# ADS1271_top.net
KiCad netlist of a schematic drawn in EAGLE
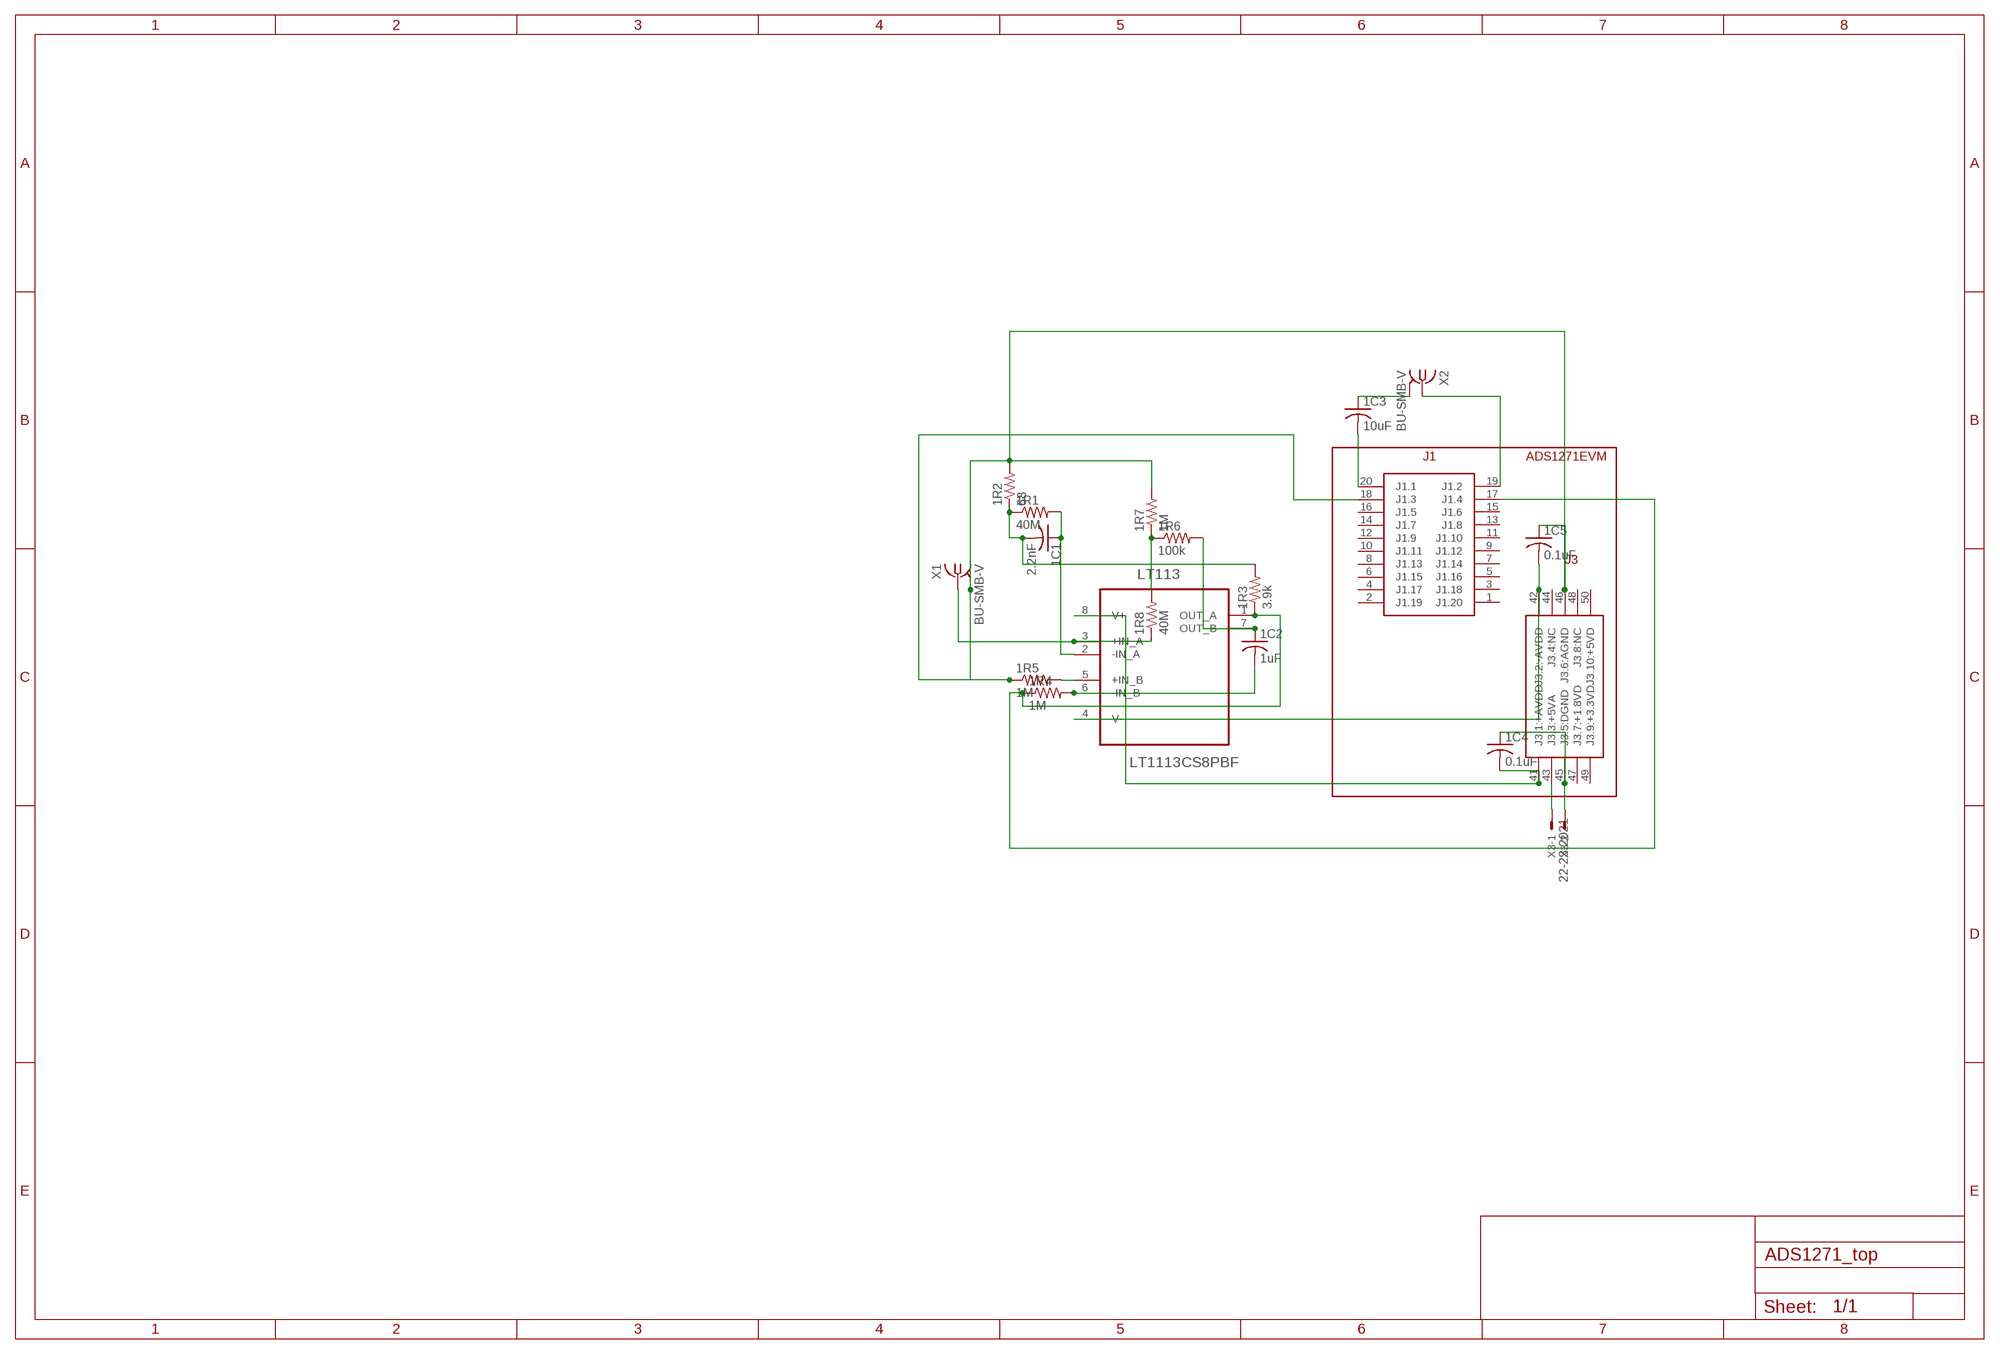
[diagram p0: schematic, sheet 1]

(export (version "E")
  (design (tool "Eeschema 10.0.6"))
  (components
    (comp (ref "1C1")
      (value "2.2nF")
      (footprint "eagle-import:ADAFRUIT_C0805K")
      (libsource (lib "eagle-import") (part "ADAFRUIT_C-USC0805K"))
    )
    (comp (ref "1C2")
      (value "1uF")
      (footprint "eagle-import:ADAFRUIT_C0805K")
      (libsource (lib "eagle-import") (part "ADAFRUIT_C-USC0805K"))
    )
    (comp (ref "1C3")
      (value "10uF")
      (footprint "eagle-import:ADAFRUIT_C0805K")
      (libsource (lib "eagle-import") (part "ADAFRUIT_C-USC0805K"))
    )
    (comp (ref "1C4")
      (value "0.1uF")
      (footprint "eagle-import:ADAFRUIT_C0805K")
      (libsource (lib "eagle-import") (part "ADAFRUIT_C-USC0805K"))
    )
    (comp (ref "1C5")
      (value "0.1uF")
      (footprint "eagle-import:ADAFRUIT_C0805K")
      (libsource (lib "eagle-import") (part "ADAFRUIT_C-USC0805K"))
    )
    (comp (ref "1R1")
      (value "40M")
      (footprint "eagle-import:ADAFRUIT_R0805")
      (libsource (lib "eagle-import") (part "ADAFRUIT_R-US_R0805"))
    )
    (comp (ref "1R2")
      (value "68")
      (footprint "eagle-import:ADAFRUIT_R0805")
      (libsource (lib "eagle-import") (part "ADAFRUIT_R-US_R0805"))
    )
    (comp (ref "1R3")
      (value "3.9k")
      (footprint "eagle-import:ADAFRUIT_R0805")
      (libsource (lib "eagle-import") (part "ADAFRUIT_R-US_R0805"))
    )
    (comp (ref "1R4")
      (value "1M")
      (footprint "eagle-import:ADAFRUIT_R0805")
      (libsource (lib "eagle-import") (part "ADAFRUIT_R-US_R0805"))
    )
    (comp (ref "1R5")
      (value "1M")
      (footprint "eagle-import:ADAFRUIT_R0805")
      (libsource (lib "eagle-import") (part "ADAFRUIT_R-US_R0805"))
    )
    (comp (ref "1R6")
      (value "100k")
      (footprint "eagle-import:ADAFRUIT_R0805")
      (libsource (lib "eagle-import") (part "ADAFRUIT_R-US_R0805"))
    )
    (comp (ref "1R7")
      (value "1M")
      (footprint "eagle-import:ADAFRUIT_R0805")
      (libsource (lib "eagle-import") (part "ADAFRUIT_R-US_R0805"))
    )
    (comp (ref "1R8")
      (value "40M")
      (footprint "eagle-import:ADAFRUIT_R0805")
      (libsource (lib "eagle-import") (part "ADAFRUIT_R-US_R0805"))
    )
    (comp (ref "ADS1271_CONNECTORS")
      (value "BENS_LIBRARY_ADS1271EVM_PART")
      (footprint "eagle-import:BENS_LIBRARY_ADS1271EVM_PART")
      (libsource (lib "eagle-import") (part "BENS_LIBRARY_ADS1271EVM_PART"))
    )
    (comp (ref "LT113")
      (value "LT1113CS8PBF")
      (footprint "eagle-import:SOIC127P600X175-8N")
      (fields (field (name "MPN") "LT1113CS8#PBF"))
      (libsource (lib "eagle-import") (part "LT1113CS8PBF"))
    )
    (comp (ref "X1")
      (value "BU-SMB-V")
      (footprint "eagle-import:BU-SMB-V")
      (libsource (lib "eagle-import") (part "BU-SMB-V"))
    )
    (comp (ref "X2")
      (value "BU-SMB-V")
      (footprint "eagle-import:BU-SMB-V")
      (libsource (lib "eagle-import") (part "BU-SMB-V"))
    )
    (comp (ref "X3")
      (value "22-23-2021")
      (footprint "eagle-import:22-23-2021")
      (fields (field (name "MF") "MOLEX"))
      (libsource (lib "eagle-import") (part "22-23-2021"))
    )
  )
  (nets
    (net (code "1") (name "/ADC1_POS") (class "Default")
      (node (ref "1C4") (pin "1") (pinfunction "1_1") (pintype "passive"))
      (node (ref "1C5") (pin "1") (pinfunction "1_1") (pintype "passive"))
      (node (ref "1R2") (pin "2") (pinfunction "2_2") (pintype "passive"))
      (node (ref "1R5") (pin "1") (pinfunction "1_1") (pintype "passive"))
      (node (ref "1R7") (pin "2") (pinfunction "2_2") (pintype "passive"))
      (node (ref "ADS1271_CONNECTORS") (pin "18") (pinfunction "J1.3_18") (pintype "bidirectional"))
      (node (ref "ADS1271_CONNECTORS") (pin "45") (pinfunction "J3.5:DGND_45") (pintype "bidirectional"))
      (node (ref "ADS1271_CONNECTORS") (pin "46") (pinfunction "J3.6:AGND_46") (pintype "bidirectional"))
      (node (ref "X1") (pin "2") (pinfunction "2_2") (pintype "passive"))
      (node (ref "X1") (pin "3") (pinfunction "2_3") (pintype "passive"))
      (node (ref "X1") (pin "4") (pinfunction "2_4") (pintype "passive"))
      (node (ref "X1") (pin "5") (pinfunction "2_5") (pintype "passive"))
      (node (ref "X3") (pin "2") (pinfunction "S_2") (pintype "passive"))
    )
    (net (code "2") (name "Net-(1C1-Pad2)") (class "Default")
      (node (ref "1C1") (pin "2") (pinfunction "2_2") (pintype "passive"))
      (node (ref "1R1") (pin "1") (pinfunction "1_1") (pintype "passive"))
      (node (ref "1R2") (pin "1") (pinfunction "1_1") (pintype "passive"))
      (node (ref "1R3") (pin "2") (pinfunction "2_2") (pintype "passive"))
    )
    (net (code "3") (name "Net-(1C3-Pad1)") (class "Default")
      (node (ref "1C3") (pin "1") (pinfunction "1_1") (pintype "passive"))
      (node (ref "X2") (pin "2") (pinfunction "2_2") (pintype "passive"))
      (node (ref "X2") (pin "3") (pinfunction "2_3") (pintype "passive"))
      (node (ref "X2") (pin "4") (pinfunction "2_4") (pintype "passive"))
      (node (ref "X2") (pin "5") (pinfunction "2_5") (pintype "passive"))
    )
    (net (code "4") (name "Net-(1R6-Pad1)") (class "Default")
      (node (ref "1R6") (pin "1") (pinfunction "1_1") (pintype "passive"))
      (node (ref "1R7") (pin "1") (pinfunction "1_1") (pintype "passive"))
      (node (ref "1R8") (pin "2") (pinfunction "2_2") (pintype "passive"))
    )
    (net (code "5") (name "Net-(ADS1271_CONNECTORS-J1.1)") (class "Default")
      (node (ref "1C3") (pin "2") (pinfunction "2_2") (pintype "passive"))
      (node (ref "ADS1271_CONNECTORS") (pin "20") (pinfunction "J1.1_20") (pintype "bidirectional"))
    )
    (net (code "6") (name "Net-(ADS1271_CONNECTORS-J1.2)") (class "Default")
      (node (ref "ADS1271_CONNECTORS") (pin "19") (pinfunction "J1.2_19") (pintype "bidirectional"))
      (node (ref "X2") (pin "1") (pinfunction "1_1") (pintype "passive"))
    )
    (net (code "7") (name "Net-(ADS1271_CONNECTORS-J1.4)") (class "Default")
      (node (ref "1R3") (pin "1") (pinfunction "1_1") (pintype "passive"))
      (node (ref "1R4") (pin "1") (pinfunction "1_1") (pintype "passive"))
      (node (ref "ADS1271_CONNECTORS") (pin "17") (pinfunction "J1.4_17") (pintype "bidirectional"))
      (node (ref "LT113") (pin "1") (pinfunction "OUT_A_1") (pintype "output"))
    )
    (net (code "8") (name "Net-(ADS1271_CONNECTORS-J3.1:+AVDD)") (class "Default")
      (node (ref "1C4") (pin "2") (pinfunction "2_2") (pintype "passive"))
      (node (ref "ADS1271_CONNECTORS") (pin "41") (pinfunction "J3.1:+AVDD_41") (pintype "bidirectional"))
      (node (ref "LT113") (pin "8") (pinfunction "V+_8") (pintype "power_in"))
    )
    (net (code "9") (name "Net-(ADS1271_CONNECTORS-J3.2:-AVDD)") (class "Default")
      (node (ref "1C5") (pin "2") (pinfunction "2_2") (pintype "passive"))
      (node (ref "ADS1271_CONNECTORS") (pin "42") (pinfunction "J3.2:-AVDD_42") (pintype "bidirectional"))
      (node (ref "LT113") (pin "4") (pinfunction "V-_4") (pintype "power_in"))
    )
    (net (code "10") (name "Net-(ADS1271_CONNECTORS-J3.3:+5VA)") (class "Default")
      (node (ref "ADS1271_CONNECTORS") (pin "43") (pinfunction "J3.3:+5VA_43") (pintype "bidirectional"))
      (node (ref "X3") (pin "1") (pinfunction "S_1") (pintype "passive"))
    )
    (net (code "11") (name "Net-(LT113-+IN_A)") (class "Default")
      (node (ref "1R8") (pin "1") (pinfunction "1_1") (pintype "passive"))
      (node (ref "LT113") (pin "3") (pinfunction "+IN_A_3") (pintype "input"))
      (node (ref "X1") (pin "1") (pinfunction "1_1") (pintype "passive"))
    )
    (net (code "12") (name "Net-(LT113-+IN_B)") (class "Default")
      (node (ref "1R5") (pin "2") (pinfunction "2_2") (pintype "passive"))
      (node (ref "LT113") (pin "5") (pinfunction "+IN_B_5") (pintype "input"))
    )
    (net (code "13") (name "Net-(LT113--IN_A)") (class "Default")
      (node (ref "1C1") (pin "1") (pinfunction "1_1") (pintype "passive"))
      (node (ref "1R1") (pin "2") (pinfunction "2_2") (pintype "passive"))
      (node (ref "LT113") (pin "2") (pinfunction "-IN_A_2") (pintype "input"))
    )
    (net (code "14") (name "Net-(LT113--IN_B)") (class "Default")
      (node (ref "1C2") (pin "2") (pinfunction "2_2") (pintype "passive"))
      (node (ref "1R4") (pin "2") (pinfunction "2_2") (pintype "passive"))
      (node (ref "LT113") (pin "6") (pinfunction "-IN_B_6") (pintype "input"))
    )
    (net (code "15") (name "Net-(LT113-OUT_B)") (class "Default")
      (node (ref "1C2") (pin "1") (pinfunction "1_1") (pintype "passive"))
      (node (ref "1R6") (pin "2") (pinfunction "2_2") (pintype "passive"))
      (node (ref "LT113") (pin "7") (pinfunction "OUT_B_7") (pintype "output"))
    )
    (net (code "16") (name "unconnected-(ADS1271_CONNECTORS-J1.5-Pad16)") (class "Default")
      (node (ref "ADS1271_CONNECTORS") (pin "16") (pinfunction "J1.5_16") (pintype "bidirectional"))
    )
    (net (code "17") (name "unconnected-(ADS1271_CONNECTORS-J1.6-Pad15)") (class "Default")
      (node (ref "ADS1271_CONNECTORS") (pin "15") (pinfunction "J1.6_15") (pintype "bidirectional"))
    )
    (net (code "18") (name "unconnected-(ADS1271_CONNECTORS-J1.7-Pad14)") (class "Default")
      (node (ref "ADS1271_CONNECTORS") (pin "14") (pinfunction "J1.7_14") (pintype "bidirectional"))
    )
    (net (code "19") (name "unconnected-(ADS1271_CONNECTORS-J1.8-Pad13)") (class "Default")
      (node (ref "ADS1271_CONNECTORS") (pin "13") (pinfunction "J1.8_13") (pintype "bidirectional"))
    )
    (net (code "20") (name "unconnected-(ADS1271_CONNECTORS-J1.9-Pad12)") (class "Default")
      (node (ref "ADS1271_CONNECTORS") (pin "12") (pinfunction "J1.9_12") (pintype "bidirectional"))
    )
    (net (code "21") (name "unconnected-(ADS1271_CONNECTORS-J1.10-Pad11)") (class "Default")
      (node (ref "ADS1271_CONNECTORS") (pin "11") (pinfunction "J1.10_11") (pintype "bidirectional"))
    )
    (net (code "22") (name "unconnected-(ADS1271_CONNECTORS-J1.11-Pad10)") (class "Default")
      (node (ref "ADS1271_CONNECTORS") (pin "10") (pinfunction "J1.11_10") (pintype "bidirectional"))
    )
    (net (code "23") (name "unconnected-(ADS1271_CONNECTORS-J1.12-Pad9)") (class "Default")
      (node (ref "ADS1271_CONNECTORS") (pin "9") (pinfunction "J1.12_9") (pintype "bidirectional"))
    )
    (net (code "24") (name "unconnected-(ADS1271_CONNECTORS-J1.13-Pad8)") (class "Default")
      (node (ref "ADS1271_CONNECTORS") (pin "8") (pinfunction "J1.13_8") (pintype "bidirectional"))
    )
    (net (code "25") (name "unconnected-(ADS1271_CONNECTORS-J1.14-Pad7)") (class "Default")
      (node (ref "ADS1271_CONNECTORS") (pin "7") (pinfunction "J1.14_7") (pintype "bidirectional"))
    )
    (net (code "26") (name "unconnected-(ADS1271_CONNECTORS-J1.15-Pad6)") (class "Default")
      (node (ref "ADS1271_CONNECTORS") (pin "6") (pinfunction "J1.15_6") (pintype "bidirectional"))
    )
    (net (code "27") (name "unconnected-(ADS1271_CONNECTORS-J1.16-Pad5)") (class "Default")
      (node (ref "ADS1271_CONNECTORS") (pin "5") (pinfunction "J1.16_5") (pintype "bidirectional"))
    )
    (net (code "28") (name "unconnected-(ADS1271_CONNECTORS-J1.17-Pad4)") (class "Default")
      (node (ref "ADS1271_CONNECTORS") (pin "4") (pinfunction "J1.17_4") (pintype "bidirectional"))
    )
    (net (code "29") (name "unconnected-(ADS1271_CONNECTORS-J1.18-Pad3)") (class "Default")
      (node (ref "ADS1271_CONNECTORS") (pin "3") (pinfunction "J1.18_3") (pintype "bidirectional"))
    )
    (net (code "30") (name "unconnected-(ADS1271_CONNECTORS-J1.19-Pad2)") (class "Default")
      (node (ref "ADS1271_CONNECTORS") (pin "2") (pinfunction "J1.19_2") (pintype "bidirectional"))
    )
    (net (code "31") (name "unconnected-(ADS1271_CONNECTORS-J1.20-Pad1)") (class "Default")
      (node (ref "ADS1271_CONNECTORS") (pin "1") (pinfunction "J1.20_1") (pintype "bidirectional"))
    )
    (net (code "32") (name "unconnected-(ADS1271_CONNECTORS-J3.4:NC-Pad44)") (class "Default")
      (node (ref "ADS1271_CONNECTORS") (pin "44") (pinfunction "J3.4:NC_44") (pintype "bidirectional"))
    )
    (net (code "33") (name "unconnected-(ADS1271_CONNECTORS-J3.7:+1.8VD-Pad47)") (class "Default")
      (node (ref "ADS1271_CONNECTORS") (pin "47") (pinfunction "J3.7:+1.8VD_47") (pintype "bidirectional"))
    )
    (net (code "34") (name "unconnected-(ADS1271_CONNECTORS-J3.8:NC-Pad48)") (class "Default")
      (node (ref "ADS1271_CONNECTORS") (pin "48") (pinfunction "J3.8:NC_48") (pintype "bidirectional"))
    )
    (net (code "35") (name "unconnected-(ADS1271_CONNECTORS-J3.9:+3.3VD-Pad49)") (class "Default")
      (node (ref "ADS1271_CONNECTORS") (pin "49") (pinfunction "J3.9:+3.3VD_49") (pintype "bidirectional"))
    )
    (net (code "36") (name "unconnected-(ADS1271_CONNECTORS-J3.10:+5VD-Pad50)") (class "Default")
      (node (ref "ADS1271_CONNECTORS") (pin "50") (pinfunction "J3.10:+5VD_50") (pintype "bidirectional"))
    )
  )
)
